# Righ_CH.net
KiCad netlist of a schematic drawn in Altium Designer
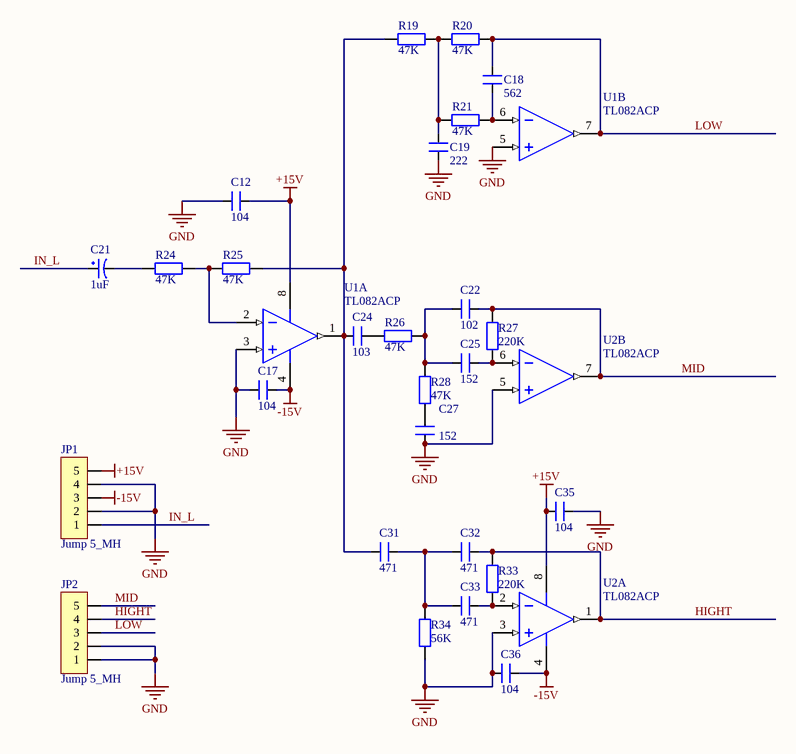
[diagram p0: Righ_CH.SchDoc]

(export (version "E")
  (design (tool "Eeschema 10.0.6"))
  (components
    (comp (ref "C12")
      (value "104")
      (footprint "TU_GOM(104-->105pF)")
      (libsource (lib "MH_DA_THU_VIEN_16122016") (part "TU_MICA_ 104 100V(2A104J)_MH"))
    )
    (comp (ref "C17")
      (value "104")
      (footprint "TU_GOM(104-->105pF)")
      (libsource (lib "MH_DA_THU_VIEN_16122016") (part "TU_MICA_ 104 100V(2A104J)_MH"))
    )
    (comp (ref "C18")
      (value "562")
      (footprint "WIMA-FKP-2-1nF")
      (libsource (lib "MH_DA_THU_VIEN_16122016") (part "TU_MICA_ 104 100V(2A104J)_MH"))
    )
    (comp (ref "C19")
      (value "222")
      (footprint "WIMA-FKP-2-1nF")
      (libsource (lib "MH_DA_THU_VIEN_16122016") (part "TU_MICA_ 104 100V(2A104J)_MH"))
    )
    (comp (ref "C21")
      (value "1uF")
      (footprint "CP1/3.0")
      (description "TU_HOA_4.7uF_100V_MH")
      (libsource (lib "MH_DA_THU_VIEN_16122016") (part "TU_HOA_4.7uF_100V_MH"))
    )
    (comp (ref "C22")
      (value "102")
      (footprint "WIMA-FKP-2-1nF")
      (libsource (lib "MH_DA_THU_VIEN_16122016") (part "TU_MICA_ 104 100V(2A104J)_MH"))
    )
    (comp (ref "C24")
      (value "103")
      (footprint "WIMA-FKP-2-1nF")
      (libsource (lib "MH_DA_THU_VIEN_16122016") (part "TU_MICA_ 104 100V(2A104J)_MH"))
    )
    (comp (ref "C25")
      (value "152")
      (footprint "WIMA-FKP-2-1nF")
      (libsource (lib "MH_DA_THU_VIEN_16122016") (part "TU_MICA_ 104 100V(2A104J)_MH"))
    )
    (comp (ref "C27")
      (value "152")
      (footprint "WIMA-FKP-2-1nF")
      (libsource (lib "MH_DA_THU_VIEN_16122016") (part "TU_MICA_ 104 100V(2A104J)_MH"))
    )
    (comp (ref "C31")
      (value "471")
      (footprint "WIMA-FKP-2-1nF")
      (libsource (lib "MH_DA_THU_VIEN_16122016") (part "TU_MICA_ 104 100V(2A104J)_MH"))
    )
    (comp (ref "C32")
      (value "471")
      (footprint "WIMA-FKP-2-1nF")
      (libsource (lib "MH_DA_THU_VIEN_16122016") (part "TU_MICA_ 104 100V(2A104J)_MH"))
    )
    (comp (ref "C33")
      (value "471")
      (footprint "WIMA-FKP-2-1nF")
      (libsource (lib "MH_DA_THU_VIEN_16122016") (part "TU_MICA_ 104 100V(2A104J)_MH"))
    )
    (comp (ref "C35")
      (value "104")
      (footprint "TU_GOM(104-->105pF)")
      (libsource (lib "MH_DA_THU_VIEN_16122016") (part "TU_MICA_ 104 100V(2A104J)_MH"))
    )
    (comp (ref "C36")
      (value "104")
      (footprint "TU_GOM(104-->105pF)")
      (libsource (lib "MH_DA_THU_VIEN_16122016") (part "TU_MICA_ 104 100V(2A104J)_MH"))
    )
    (comp (ref "JP1")
      (value "Jump 5_MH")
      (footprint "Jump 5")
      (description "Jump 5P 2.54")
      (libsource (lib "MH_DA_THU_VIEN_16122016") (part "Jump 5_MH"))
    )
    (comp (ref "JP2")
      (value "Jump 5_MH")
      (footprint "Jump 5")
      (description "Jump 5P 2.54")
      (libsource (lib "MH_DA_THU_VIEN_16122016") (part "Jump 5_MH"))
    )
    (comp (ref "R19")
      (value "47K")
      (footprint "TRO_VACH_ 1/4W")
      (description "Resistor")
      (fields (field (name "PUBLISHER") "Altium Limited"))
      (libsource (lib "") (part "TRO_VACH_1/2W_MH_1"))
    )
    (comp (ref "R20")
      (value "47K")
      (footprint "TRO_VACH_ 1/4W")
      (description "Resistor")
      (fields (field (name "PUBLISHER") "Altium Limited"))
      (libsource (lib "") (part "TRO_VACH_1/2W_MH_1"))
    )
    (comp (ref "R21")
      (value "47K")
      (footprint "TRO_VACH_ 1/4W")
      (description "Resistor")
      (fields (field (name "PUBLISHER") "Altium Limited"))
      (libsource (lib "") (part "TRO_VACH_1/2W_MH_1"))
    )
    (comp (ref "R24")
      (value "47K")
      (footprint "TRO_VACH_ 1/4W")
      (description "Resistor")
      (fields (field (name "PUBLISHER") "Altium Limited"))
      (libsource (lib "") (part "TRO_VACH_1/2W_MH_1"))
    )
    (comp (ref "R25")
      (value "47K")
      (footprint "TRO_VACH_ 1/4W")
      (description "Resistor")
      (fields (field (name "PUBLISHER") "Altium Limited"))
      (libsource (lib "") (part "TRO_VACH_1/2W_MH_1"))
    )
    (comp (ref "R26")
      (value "47K")
      (footprint "TRO_VACH_ 1/4W")
      (description "Resistor")
      (fields (field (name "PUBLISHER") "Altium Limited"))
      (libsource (lib "") (part "TRO_VACH_1/2W_MH_2"))
    )
    (comp (ref "R27")
      (value "220K")
      (footprint "TRO_VACH_ 1/4W")
      (description "Resistor")
      (fields (field (name "PUBLISHER") "Altium Limited"))
      (libsource (lib "MH_DA_THU_VIEN_16122016") (part "TRO_VACH_1/2W_MH"))
    )
    (comp (ref "R28")
      (value "47K")
      (footprint "TRO_VACH_ 1/4W")
      (description "Resistor")
      (fields (field (name "PUBLISHER") "Altium Limited"))
      (libsource (lib "MH_DA_THU_VIEN_16122016") (part "TRO_VACH_1/2W_MH"))
    )
    (comp (ref "R33")
      (value "220K")
      (footprint "TRO_VACH_ 1/4W")
      (description "Resistor")
      (fields (field (name "PUBLISHER") "Altium Limited"))
      (libsource (lib "MH_DA_THU_VIEN_16122016") (part "TRO_VACH_1/2W_MH"))
    )
    (comp (ref "R34")
      (value "56K")
      (footprint "TRO_VACH_ 1/4W")
      (description "Resistor")
      (fields (field (name "PUBLISHER") "Altium Limited"))
      (libsource (lib "MH_DA_THU_VIEN_16122016") (part "TRO_VACH_1/2W_MH"))
    )
    (comp (ref "U1")
      (value "TL082ACP")
      (footprint "DIP8")
      (description "JFET-Input Operational Amplifier")
      (fields (field (name "PUBLISHER") "Altium Limited"))
      (libsource (lib "Schlib1") (part "TL082ACP"))
    )
    (comp (ref "U2")
      (value "TL082ACP")
      (footprint "DIP8")
      (description "JFET-Input Operational Amplifier")
      (fields (field (name "PUBLISHER") "Altium Limited"))
      (libsource (lib "Schlib1") (part "TL082ACP"))
    )
  )
  (nets
    (net (code "1") (name "+15V") (class "Default")
      (node (ref "C12") (pin "2") (pinfunction "2_2") (pintype "passive"))
      (node (ref "C35") (pin "2") (pinfunction "2_2") (pintype "passive"))
      (node (ref "JP1") (pin "5") (pinfunction "5_5") (pintype "passive"))
      (node (ref "U1") (pin "8") (pinfunction "V+_8") (pintype "power_in"))
      (node (ref "U2") (pin "8") (pinfunction "V+_8") (pintype "power_in"))
    )
    (net (code "2") (name "-15V") (class "Default")
      (node (ref "C17") (pin "2") (pinfunction "2_2") (pintype "passive"))
      (node (ref "C36") (pin "1") (pinfunction "1_1") (pintype "passive"))
      (node (ref "JP1") (pin "3") (pinfunction "3_3") (pintype "passive"))
      (node (ref "U1") (pin "4") (pinfunction "V-_4") (pintype "power_in"))
      (node (ref "U2") (pin "4") (pinfunction "V-_4") (pintype "power_in"))
    )
    (net (code "3") (name "/HIGHT") (class "Default")
      (node (ref "C32") (pin "1") (pinfunction "1_1") (pintype "passive"))
      (node (ref "JP2") (pin "4") (pinfunction "4_4") (pintype "passive"))
      (node (ref "R33") (pin "2") (pinfunction "2_2") (pintype "passive"))
      (node (ref "U2") (pin "1") (pinfunction "OUT_1") (pintype "output"))
    )
    (net (code "4") (name "/IN_L") (class "Default")
      (node (ref "C21") (pin "1") (pinfunction "1_1") (pintype "passive"))
      (node (ref "JP1") (pin "1") (pinfunction "1_1") (pintype "passive"))
    )
    (net (code "5") (name "/LOW") (class "Default")
      (node (ref "C18") (pin "2") (pinfunction "2_2") (pintype "passive"))
      (node (ref "JP2") (pin "3") (pinfunction "3_3") (pintype "passive"))
      (node (ref "R20") (pin "2") (pinfunction "2_2") (pintype "passive"))
      (node (ref "U1") (pin "7") (pinfunction "OUT_7") (pintype "output"))
    )
    (net (code "6") (name "/MID") (class "Default")
      (node (ref "C22") (pin "1") (pinfunction "1_1") (pintype "passive"))
      (node (ref "JP2") (pin "5") (pinfunction "5_5") (pintype "passive"))
      (node (ref "R27") (pin "2") (pinfunction "2_2") (pintype "passive"))
      (node (ref "U2") (pin "7") (pinfunction "OUT_7") (pintype "output"))
    )
    (net (code "7") (name "GND") (class "Default")
      (node (ref "C12") (pin "1") (pinfunction "1_1") (pintype "passive"))
      (node (ref "C17") (pin "1") (pinfunction "1_1") (pintype "passive"))
      (node (ref "C19") (pin "1") (pinfunction "1_1") (pintype "passive"))
      (node (ref "C27") (pin "2") (pinfunction "2_2") (pintype "passive"))
      (node (ref "C35") (pin "1") (pinfunction "1_1") (pintype "passive"))
      (node (ref "C36") (pin "2") (pinfunction "2_2") (pintype "passive"))
      (node (ref "JP1") (pin "2") (pinfunction "2_2") (pintype "passive"))
      (node (ref "JP1") (pin "4") (pinfunction "4_4") (pintype "passive"))
      (node (ref "JP2") (pin "1") (pinfunction "1_1") (pintype "passive"))
      (node (ref "JP2") (pin "2") (pinfunction "2_2") (pintype "passive"))
      (node (ref "R34") (pin "1") (pinfunction "1_1") (pintype "passive"))
      (node (ref "U1") (pin "3") (pinfunction "IN+_3") (pintype "input"))
      (node (ref "U1") (pin "5") (pinfunction "IN+_5") (pintype "input"))
      (node (ref "U2") (pin "3") (pinfunction "IN+_3") (pintype "input"))
      (node (ref "U2") (pin "5") (pinfunction "IN+_5") (pintype "input"))
    )
    (net (code "8") (name "Net-(C19-Pad2)") (class "Default")
      (node (ref "C19") (pin "2") (pinfunction "2_2") (pintype "passive"))
      (node (ref "R19") (pin "2") (pinfunction "2_2") (pintype "passive"))
      (node (ref "R20") (pin "1") (pinfunction "1_1") (pintype "passive"))
      (node (ref "R21") (pin "1") (pinfunction "1_1") (pintype "passive"))
    )
    (net (code "9") (name "Net-(C21-Pad2)") (class "Default")
      (node (ref "C21") (pin "2") (pinfunction "2_2") (pintype "passive"))
      (node (ref "R24") (pin "1") (pinfunction "1_1") (pintype "passive"))
    )
    (net (code "10") (name "Net-(C22-Pad2)") (class "Default")
      (node (ref "C22") (pin "2") (pinfunction "2_2") (pintype "passive"))
      (node (ref "C25") (pin "2") (pinfunction "2_2") (pintype "passive"))
      (node (ref "R26") (pin "1") (pinfunction "1_1") (pintype "passive"))
      (node (ref "R28") (pin "2") (pinfunction "2_2") (pintype "passive"))
    )
    (net (code "11") (name "Net-(C24-Pad2)") (class "Default")
      (node (ref "C24") (pin "2") (pinfunction "2_2") (pintype "passive"))
      (node (ref "R26") (pin "2") (pinfunction "2_2") (pintype "passive"))
    )
    (net (code "12") (name "Net-(C27-Pad1)") (class "Default")
      (node (ref "C27") (pin "1") (pinfunction "1_1") (pintype "passive"))
      (node (ref "R28") (pin "1") (pinfunction "1_1") (pintype "passive"))
    )
    (net (code "13") (name "Net-(C31-Pad1)") (class "Default")
      (node (ref "C31") (pin "1") (pinfunction "1_1") (pintype "passive"))
      (node (ref "C32") (pin "2") (pinfunction "2_2") (pintype "passive"))
      (node (ref "C33") (pin "2") (pinfunction "2_2") (pintype "passive"))
      (node (ref "R34") (pin "2") (pinfunction "2_2") (pintype "passive"))
    )
    (net (code "14") (name "Net-(U1A-IN-)") (class "Default")
      (node (ref "R24") (pin "2") (pinfunction "2_2") (pintype "passive"))
      (node (ref "R25") (pin "1") (pinfunction "1_1") (pintype "passive"))
      (node (ref "U1") (pin "2") (pinfunction "IN-_2") (pintype "input"))
    )
    (net (code "15") (name "Net-(U1A-OUT)") (class "Default")
      (node (ref "C24") (pin "1") (pinfunction "1_1") (pintype "passive"))
      (node (ref "C31") (pin "2") (pinfunction "2_2") (pintype "passive"))
      (node (ref "R19") (pin "1") (pinfunction "1_1") (pintype "passive"))
      (node (ref "R25") (pin "2") (pinfunction "2_2") (pintype "passive"))
      (node (ref "U1") (pin "1") (pinfunction "OUT_1") (pintype "output"))
    )
    (net (code "16") (name "Net-(U1B-IN-)") (class "Default")
      (node (ref "C18") (pin "1") (pinfunction "1_1") (pintype "passive"))
      (node (ref "R21") (pin "2") (pinfunction "2_2") (pintype "passive"))
      (node (ref "U1") (pin "6") (pinfunction "IN-_6") (pintype "input"))
    )
    (net (code "17") (name "Net-(U2A-IN-)") (class "Default")
      (node (ref "C33") (pin "1") (pinfunction "1_1") (pintype "passive"))
      (node (ref "R33") (pin "1") (pinfunction "1_1") (pintype "passive"))
      (node (ref "U2") (pin "2") (pinfunction "IN-_2") (pintype "input"))
    )
    (net (code "18") (name "Net-(U2B-IN-)") (class "Default")
      (node (ref "C25") (pin "1") (pinfunction "1_1") (pintype "passive"))
      (node (ref "R27") (pin "1") (pinfunction "1_1") (pintype "passive"))
      (node (ref "U2") (pin "6") (pinfunction "IN-_6") (pintype "input"))
    )
  )
)
